# tinyled.net
KiCad netlist of a schematic drawn in EAGLE
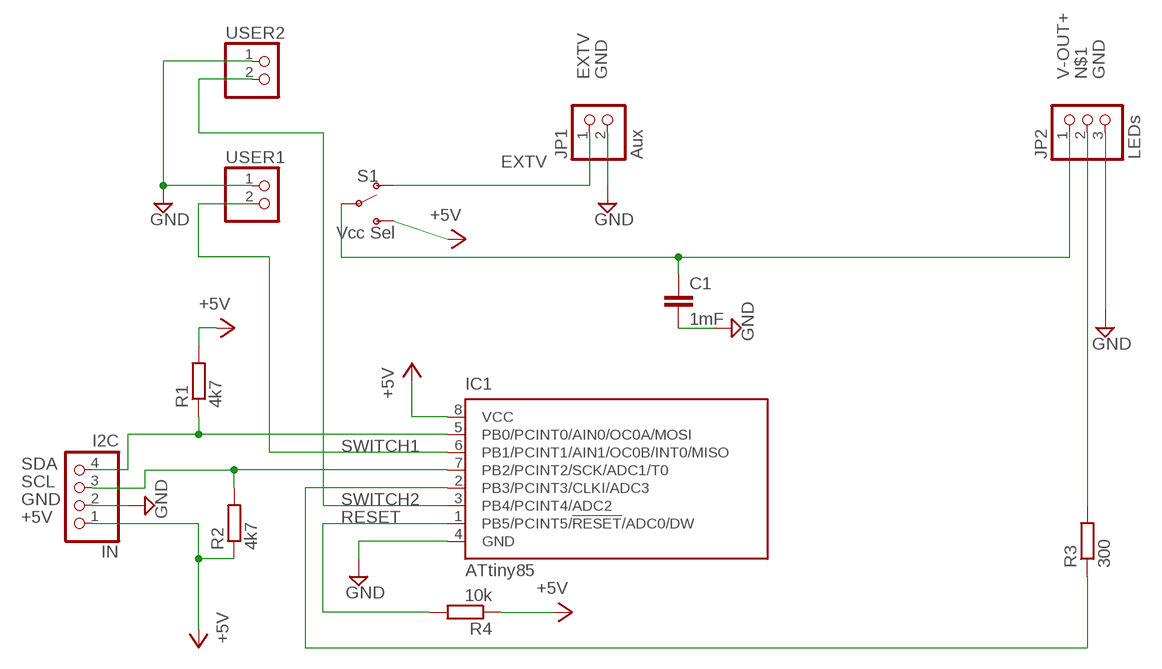
[diagram p0: schematic, sheet 1]

(export (version "E")
  (design (tool "Eeschema 10.0.6"))
  (components
    (comp (ref "C1")
      (value "1mF")
      (footprint "eagle-import:C050-025X075")
      (libsource (lib "eagle-import") (part "C-EU050-025X075"))
    )
    (comp (ref "IC1")
      (value "ATtiny85")
      (footprint "eagle-import:DIL08")
      (fields (field (name "MPN") "ATTINY13-20PU"))
      (libsource (lib "eagle-import") (part "TINY13PU-20"))
    )
    (comp (ref "IN")
      (value "I2C")
      (footprint "eagle-import:1X04_90")
      (libsource (lib "eagle-import") (part "PINHD-1X4/90"))
    )
    (comp (ref "JP1")
      (value "Aux")
      (footprint "eagle-import:1X02_90")
      (libsource (lib "eagle-import") (part "PINHD-1X2/90"))
    )
    (comp (ref "JP2")
      (value "LEDs")
      (footprint "eagle-import:1X03_90")
      (libsource (lib "eagle-import") (part "PINHD-1X3/90"))
    )
    (comp (ref "R1")
      (value "4k7")
      (footprint "eagle-import:0204_7")
      (libsource (lib "eagle-import") (part "R0204/7"))
    )
    (comp (ref "R2")
      (value "4k7")
      (footprint "eagle-import:0204_7")
      (libsource (lib "eagle-import") (part "R0204/7"))
    )
    (comp (ref "R3")
      (value "300")
      (footprint "eagle-import:0204_7")
      (libsource (lib "eagle-import") (part "R0204/7"))
    )
    (comp (ref "R4")
      (value "10k")
      (footprint "eagle-import:0204_7")
      (libsource (lib "eagle-import") (part "R0204/7"))
    )
    (comp (ref "S1")
      (value "Vcc Sel")
      (footprint "eagle-import:SWITCH_SPDT_PTH_11.6X4.0MM")
      (libsource (lib "eagle-import") (part "SWITCH-SPDT-PTH-11.6X4.0MM"))
    )
    (comp (ref "USER1")
      (value "PINHD-1X2")
      (footprint "eagle-import:1X02")
      (libsource (lib "eagle-import") (part "PINHD-1X2"))
    )
    (comp (ref "USER2")
      (value "PINHD-1X2")
      (footprint "eagle-import:1X02")
      (libsource (lib "eagle-import") (part "PINHD-1X2"))
    )
  )
  (nets
    (net (code "1") (name "+5V") (class "Default")
      (node (ref "IC1") (pin "8") (pinfunction "VCC_8") (pintype "power_in"))
      (node (ref "IN") (pin "1") (pinfunction "1_1") (pintype "passive"))
      (node (ref "R1") (pin "2") (pinfunction "2_2") (pintype "passive"))
      (node (ref "R2") (pin "1") (pinfunction "1_1") (pintype "passive"))
      (node (ref "R4") (pin "1") (pinfunction "1_1") (pintype "passive"))
      (node (ref "S1") (pin "3") (pinfunction "S_3") (pintype "passive"))
    )
    (net (code "2") (name "/EXTV") (class "Default")
      (node (ref "JP1") (pin "1") (pinfunction "1_1") (pintype "passive"))
      (node (ref "S1") (pin "1") (pinfunction "O_1") (pintype "passive"))
    )
    (net (code "3") (name "/N$1") (class "Default")
      (node (ref "JP2") (pin "2") (pinfunction "2_2") (pintype "passive"))
      (node (ref "R3") (pin "2") (pinfunction "2_2") (pintype "passive"))
    )
    (net (code "4") (name "/RESET") (class "Default")
      (node (ref "IC1") (pin "1") (pinfunction "PB5/PCINT5/~{RESET}/ADC0/DW_1") (pintype "bidirectional"))
      (node (ref "R4") (pin "2") (pinfunction "2_2") (pintype "passive"))
    )
    (net (code "5") (name "/SCL") (class "Default")
      (node (ref "IC1") (pin "7") (pinfunction "PB2/PCINT2/SCK/ADC1/T0_7") (pintype "bidirectional"))
      (node (ref "IN") (pin "3") (pinfunction "3_3") (pintype "passive"))
      (node (ref "R2") (pin "2") (pinfunction "2_2") (pintype "passive"))
    )
    (net (code "6") (name "/SDA") (class "Default")
      (node (ref "IC1") (pin "5") (pinfunction "PB0/PCINT0/AIN0/OC0A/MOSI_5") (pintype "bidirectional"))
      (node (ref "IN") (pin "4") (pinfunction "4_4") (pintype "passive"))
      (node (ref "R1") (pin "1") (pinfunction "1_1") (pintype "passive"))
    )
    (net (code "7") (name "/SWITCH1") (class "Default")
      (node (ref "IC1") (pin "6") (pinfunction "PB1/PCINT1/AIN1/OC0B/INT0/MISO_6") (pintype "bidirectional"))
      (node (ref "USER1") (pin "2") (pinfunction "2_2") (pintype "passive"))
    )
    (net (code "8") (name "/SWITCH2") (class "Default")
      (node (ref "IC1") (pin "3") (pinfunction "PB4/PCINT4/ADC2_3") (pintype "bidirectional"))
      (node (ref "USER2") (pin "2") (pinfunction "2_2") (pintype "passive"))
    )
    (net (code "9") (name "/V-OUT+") (class "Default")
      (node (ref "C1") (pin "1") (pinfunction "1_1") (pintype "passive"))
      (node (ref "JP2") (pin "1") (pinfunction "1_1") (pintype "passive"))
      (node (ref "S1") (pin "2") (pinfunction "P_2") (pintype "passive"))
    )
    (net (code "10") (name "GND") (class "Default")
      (node (ref "C1") (pin "2") (pinfunction "2_2") (pintype "passive"))
      (node (ref "IC1") (pin "4") (pinfunction "GND_4") (pintype "power_in"))
      (node (ref "IN") (pin "2") (pinfunction "2_2") (pintype "passive"))
      (node (ref "JP1") (pin "2") (pinfunction "2_2") (pintype "passive"))
      (node (ref "JP2") (pin "3") (pinfunction "3_3") (pintype "passive"))
      (node (ref "USER1") (pin "1") (pinfunction "1_1") (pintype "passive"))
      (node (ref "USER2") (pin "1") (pinfunction "1_1") (pintype "passive"))
    )
    (net (code "11") (name "Net-(IC1-PB3{slash}PCINT3{slash}CLKI{slash}ADC3)") (class "Default")
      (node (ref "IC1") (pin "2") (pinfunction "PB3/PCINT3/CLKI/ADC3_2") (pintype "bidirectional"))
      (node (ref "R3") (pin "1") (pinfunction "1_1") (pintype "passive"))
    )
  )
)
